# main2.net
KiCad netlist of a schematic drawn in EAGLE
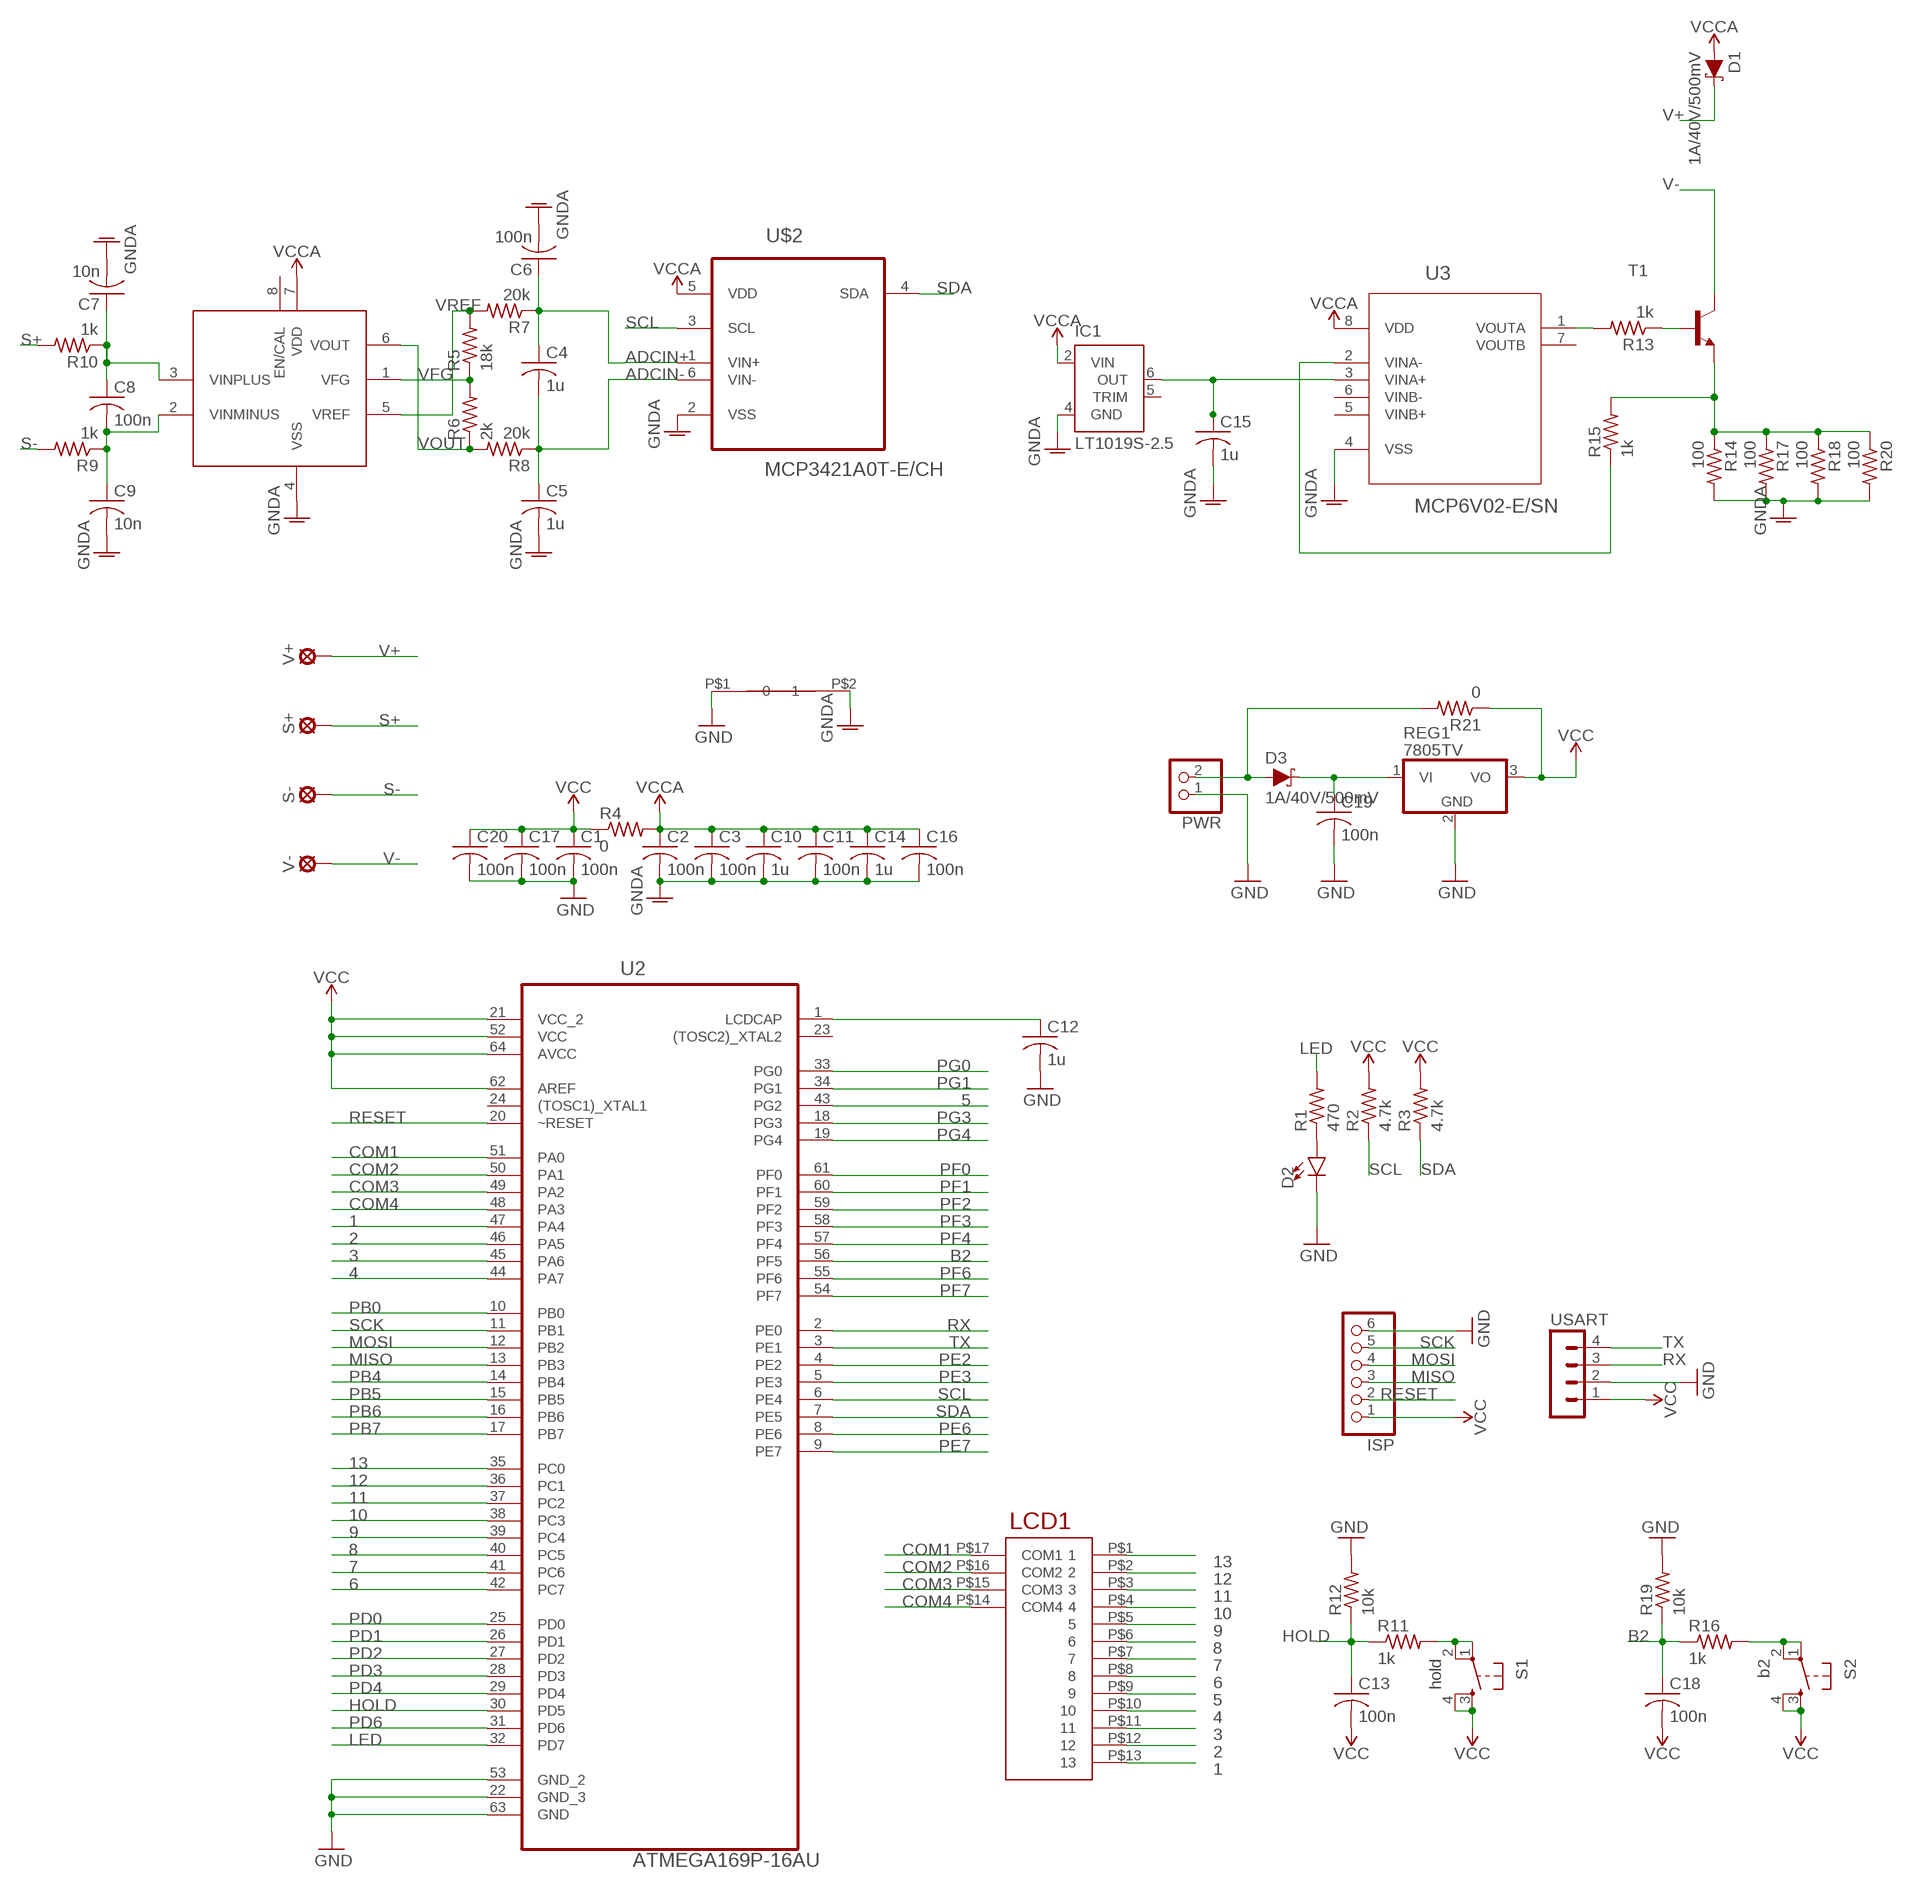
[diagram p0: schematic, sheet 1]

(export (version "E")
  (design (tool "Eeschema 10.0.6"))
  (components
    (comp (ref "C1")
      (value "100n")
      (footprint "eagle-import:C0603")
      (libsource (lib "eagle-import") (part "C-USC0603"))
    )
    (comp (ref "C2")
      (value "100n")
      (footprint "eagle-import:C0603")
      (libsource (lib "eagle-import") (part "C-USC0603"))
    )
    (comp (ref "C3")
      (value "100n")
      (footprint "eagle-import:C0603")
      (libsource (lib "eagle-import") (part "C-USC0603"))
    )
    (comp (ref "C4")
      (value "1u")
      (footprint "eagle-import:C0603")
      (libsource (lib "eagle-import") (part "C-USC0603"))
    )
    (comp (ref "C5")
      (value "1u")
      (footprint "eagle-import:C0603")
      (libsource (lib "eagle-import") (part "C-USC0603"))
    )
    (comp (ref "C6")
      (value "100n")
      (footprint "eagle-import:C0603")
      (libsource (lib "eagle-import") (part "C-USC0603"))
    )
    (comp (ref "C7")
      (value "10n")
      (footprint "eagle-import:C0603")
      (libsource (lib "eagle-import") (part "C-USC0603"))
    )
    (comp (ref "C8")
      (value "100n")
      (footprint "eagle-import:C0603")
      (libsource (lib "eagle-import") (part "C-USC0603"))
    )
    (comp (ref "C9")
      (value "10n")
      (footprint "eagle-import:C0603")
      (libsource (lib "eagle-import") (part "C-USC0603"))
    )
    (comp (ref "C10")
      (value "1u")
      (footprint "eagle-import:C0603")
      (libsource (lib "eagle-import") (part "C-USC0603"))
    )
    (comp (ref "C11")
      (value "100n")
      (footprint "eagle-import:C0603")
      (libsource (lib "eagle-import") (part "C-USC0603"))
    )
    (comp (ref "C12")
      (value "1u")
      (footprint "eagle-import:C0603")
      (libsource (lib "eagle-import") (part "C-USC0603"))
    )
    (comp (ref "C13")
      (value "100n")
      (footprint "eagle-import:C0603")
      (libsource (lib "eagle-import") (part "C-USC0603"))
    )
    (comp (ref "C14")
      (value "1u")
      (footprint "eagle-import:C0603")
      (libsource (lib "eagle-import") (part "C-USC0603"))
    )
    (comp (ref "C15")
      (value "1u")
      (footprint "eagle-import:C0603")
      (libsource (lib "eagle-import") (part "C-USC0603"))
    )
    (comp (ref "C16")
      (value "100n")
      (footprint "eagle-import:C0603")
      (libsource (lib "eagle-import") (part "C-USC0603"))
    )
    (comp (ref "C17")
      (value "100n")
      (footprint "eagle-import:C0603")
      (libsource (lib "eagle-import") (part "C-USC0603"))
    )
    (comp (ref "C18")
      (value "100n")
      (footprint "eagle-import:C0603")
      (libsource (lib "eagle-import") (part "C-USC0603"))
    )
    (comp (ref "C19")
      (value "100n")
      (footprint "eagle-import:C0603")
      (libsource (lib "eagle-import") (part "C-USC0603"))
    )
    (comp (ref "C20")
      (value "100n")
      (footprint "eagle-import:C0603")
      (libsource (lib "eagle-import") (part "C-USC0603"))
    )
    (comp (ref "D1")
      (value "1A/40V/500mV")
      (footprint "eagle-import:SMA-DIODE")
      (libsource (lib "eagle-import") (part "DIODE-SCHOTTKY-SS14"))
    )
    (comp (ref "D2")
      (value "LED5MM")
      (footprint "eagle-import:LED_5MM")
      (libsource (lib "eagle-import") (part "LED5MM"))
    )
    (comp (ref "D3")
      (value "1A/40V/500mV")
      (footprint "eagle-import:SMA-DIODE")
      (libsource (lib "eagle-import") (part "DIODE-SCHOTTKY-SS14"))
    )
    (comp (ref "IC1")
      (value "LT1019S-2.5")
      (footprint "eagle-import:SOIC8")
      (fields (field (name "MPN") "LT1019CS8-2.5#PBF"))
      (libsource (lib "eagle-import") (part "LT1019?S-2.5"))
    )
    (comp (ref "ISP")
      (value "PINHD-1X6")
      (footprint "eagle-import:1X06")
      (libsource (lib "eagle-import") (part "PINHD-1X6"))
    )
    (comp (ref "LCD1")
      (value "GDC0570_LCD")
      (footprint "eagle-import:GDC0570_LCD")
      (libsource (lib "eagle-import") (part "GDC0570_LCD"))
    )
    (comp (ref "PWR")
      (value "PINHD-1X2")
      (footprint "eagle-import:1X02")
      (libsource (lib "eagle-import") (part "PINHD-1X2"))
    )
    (comp (ref "R1")
      (value "470")
      (footprint "eagle-import:R0603")
      (libsource (lib "eagle-import") (part "R-US_R0603"))
    )
    (comp (ref "R2")
      (value "4.7k")
      (footprint "eagle-import:R0603")
      (libsource (lib "eagle-import") (part "R-US_R0603"))
    )
    (comp (ref "R3")
      (value "4.7k")
      (footprint "eagle-import:R0603")
      (libsource (lib "eagle-import") (part "R-US_R0603"))
    )
    (comp (ref "R4")
      (value "0")
      (footprint "eagle-import:0309_12")
      (libsource (lib "eagle-import") (part "R-US_0309/12"))
    )
    (comp (ref "R5")
      (value "18k")
      (footprint "eagle-import:R0603")
      (libsource (lib "eagle-import") (part "R-US_R0603"))
    )
    (comp (ref "R6")
      (value "2k")
      (footprint "eagle-import:R0603")
      (libsource (lib "eagle-import") (part "R-US_R0603"))
    )
    (comp (ref "R7")
      (value "20k")
      (footprint "eagle-import:R0603")
      (libsource (lib "eagle-import") (part "R-US_R0603"))
    )
    (comp (ref "R8")
      (value "20k")
      (footprint "eagle-import:R0603")
      (libsource (lib "eagle-import") (part "R-US_R0603"))
    )
    (comp (ref "R9")
      (value "1k")
      (footprint "eagle-import:R0603")
      (libsource (lib "eagle-import") (part "R-US_R0603"))
    )
    (comp (ref "R10")
      (value "1k")
      (footprint "eagle-import:R0603")
      (libsource (lib "eagle-import") (part "R-US_R0603"))
    )
    (comp (ref "R11")
      (value "1k")
      (footprint "eagle-import:R0603")
      (libsource (lib "eagle-import") (part "R-US_R0603"))
    )
    (comp (ref "R12")
      (value "10k")
      (footprint "eagle-import:R0603")
      (libsource (lib "eagle-import") (part "R-US_R0603"))
    )
    (comp (ref "R13")
      (value "1k")
      (footprint "eagle-import:R0603")
      (libsource (lib "eagle-import") (part "R-US_R0603"))
    )
    (comp (ref "R14")
      (value "100")
      (footprint "eagle-import:R0603")
      (libsource (lib "eagle-import") (part "R-US_R0603"))
    )
    (comp (ref "R15")
      (value "1k")
      (footprint "eagle-import:R0603")
      (libsource (lib "eagle-import") (part "R-US_R0603"))
    )
    (comp (ref "R16")
      (value "1k")
      (footprint "eagle-import:R0603")
      (libsource (lib "eagle-import") (part "R-US_R0603"))
    )
    (comp (ref "R17")
      (value "100")
      (footprint "eagle-import:R0603")
      (libsource (lib "eagle-import") (part "R-US_R0603"))
    )
    (comp (ref "R18")
      (value "100")
      (footprint "eagle-import:R0603")
      (libsource (lib "eagle-import") (part "R-US_R0603"))
    )
    (comp (ref "R19")
      (value "10k")
      (footprint "eagle-import:R0603")
      (libsource (lib "eagle-import") (part "R-US_R0603"))
    )
    (comp (ref "R20")
      (value "100")
      (footprint "eagle-import:R0603")
      (libsource (lib "eagle-import") (part "R-US_R0603"))
    )
    (comp (ref "R21")
      (value "0")
      (footprint "eagle-import:R0603")
      (libsource (lib "eagle-import") (part "R-US_R0603"))
    )
    (comp (ref "REG1")
      (value "7805TV")
      (footprint "eagle-import:TO220V")
      (libsource (lib "eagle-import") (part "78TV05"))
    )
    (comp (ref "S+")
      (value "MCS08")
      (footprint "eagle-import:MCS08")
      (libsource (lib "eagle-import") (part "MCS08"))
    )
    (comp (ref "S-")
      (value "MCS08")
      (footprint "eagle-import:MCS08")
      (libsource (lib "eagle-import") (part "MCS08"))
    )
    (comp (ref "S1")
      (value "hold")
      (footprint "eagle-import:TACTILE-PTH")
      (libsource (lib "eagle-import") (part "TAC_SWITCHPTH"))
    )
    (comp (ref "S2")
      (value "b2")
      (footprint "eagle-import:TACTILE-PTH")
      (libsource (lib "eagle-import") (part "TAC_SWITCHPTH"))
    )
    (comp (ref "T1")
      (value "MMBT3904LT1-NPN-SOT23-BEC")
      (footprint "eagle-import:SOT23-BEC")
      (libsource (lib "eagle-import") (part "-NPN-SOT23-BECMMBT3904LT1"))
    )
    (comp (ref "U$2")
      (value "MCP3421A0T-E/CH")
      (footprint "eagle-import:SOT95P270X145-6N")
      (libsource (lib "eagle-import") (part "MCP3421A0T-E/CH"))
    )
    (comp (ref "U$3")
      (value "MCP6N11")
      (footprint "eagle-import:SOIC8")
      (libsource (lib "eagle-import") (part "MCP6N11"))
    )
    (comp (ref "U$10")
      (value "SHORT32")
      (footprint "eagle-import:SHORT_32")
      (libsource (lib "eagle-import") (part "SHORT32"))
    )
    (comp (ref "U2")
      (value "ATMEGA169P-16AU")
      (footprint "eagle-import:QFP80P1600X1600X120-64N")
      (libsource (lib "eagle-import") (part "ATMEGA169P-16AU"))
    )
    (comp (ref "U3")
      (value "MCP6V02-E/SN")
      (footprint "eagle-import:SOIC127P600X175-8N")
      (libsource (lib "eagle-import") (part "MCP6V02-E/SN"))
    )
    (comp (ref "USART")
      (value "MA04-1")
      (footprint "eagle-import:MA04-1")
      (libsource (lib "eagle-import") (part "MA04-1"))
    )
    (comp (ref "V+")
      (value "MCS08")
      (footprint "eagle-import:MCS08")
      (libsource (lib "eagle-import") (part "MCS08"))
    )
    (comp (ref "V-")
      (value "MCS08")
      (footprint "eagle-import:MCS08")
      (libsource (lib "eagle-import") (part "MCS08"))
    )
  )
  (nets
    (net (code "1") (name "/1") (class "Default")
      (node (ref "LCD1") (pin "P$13") (pinfunction "13_P$13") (pintype "bidirectional"))
      (node (ref "U2") (pin "47") (pinfunction "PA4_47") (pintype "bidirectional"))
    )
    (net (code "2") (name "/2") (class "Default")
      (node (ref "LCD1") (pin "P$12") (pinfunction "12_P$12") (pintype "bidirectional"))
      (node (ref "U2") (pin "46") (pinfunction "PA5_46") (pintype "bidirectional"))
    )
    (net (code "3") (name "/3") (class "Default")
      (node (ref "LCD1") (pin "P$11") (pinfunction "11_P$11") (pintype "bidirectional"))
      (node (ref "U2") (pin "45") (pinfunction "PA6_45") (pintype "bidirectional"))
    )
    (net (code "4") (name "/4") (class "Default")
      (node (ref "LCD1") (pin "P$10") (pinfunction "10_P$10") (pintype "bidirectional"))
      (node (ref "U2") (pin "44") (pinfunction "PA7_44") (pintype "bidirectional"))
    )
    (net (code "5") (name "/5") (class "Default")
      (node (ref "LCD1") (pin "P$9") (pinfunction "9_P$9") (pintype "bidirectional"))
      (node (ref "U2") (pin "43") (pinfunction "PG2_43") (pintype "bidirectional"))
    )
    (net (code "6") (name "/6") (class "Default")
      (node (ref "LCD1") (pin "P$8") (pinfunction "8_P$8") (pintype "bidirectional"))
      (node (ref "U2") (pin "42") (pinfunction "PC7_42") (pintype "bidirectional"))
    )
    (net (code "7") (name "/7") (class "Default")
      (node (ref "LCD1") (pin "P$7") (pinfunction "7_P$7") (pintype "bidirectional"))
      (node (ref "U2") (pin "41") (pinfunction "PC6_41") (pintype "bidirectional"))
    )
    (net (code "8") (name "/8") (class "Default")
      (node (ref "LCD1") (pin "P$6") (pinfunction "6_P$6") (pintype "bidirectional"))
      (node (ref "U2") (pin "40") (pinfunction "PC5_40") (pintype "bidirectional"))
    )
    (net (code "9") (name "/9") (class "Default")
      (node (ref "LCD1") (pin "P$5") (pinfunction "5_P$5") (pintype "bidirectional"))
      (node (ref "U2") (pin "39") (pinfunction "PC4_39") (pintype "bidirectional"))
    )
    (net (code "10") (name "/10") (class "Default")
      (node (ref "LCD1") (pin "P$4") (pinfunction "4_P$4") (pintype "bidirectional"))
      (node (ref "U2") (pin "38") (pinfunction "PC3_38") (pintype "bidirectional"))
    )
    (net (code "11") (name "/11") (class "Default")
      (node (ref "LCD1") (pin "P$3") (pinfunction "3_P$3") (pintype "bidirectional"))
      (node (ref "U2") (pin "37") (pinfunction "PC2_37") (pintype "bidirectional"))
    )
    (net (code "12") (name "/12") (class "Default")
      (node (ref "LCD1") (pin "P$2") (pinfunction "2_P$2") (pintype "bidirectional"))
      (node (ref "U2") (pin "36") (pinfunction "PC1_36") (pintype "bidirectional"))
    )
    (net (code "13") (name "/13") (class "Default")
      (node (ref "LCD1") (pin "P$1") (pinfunction "1_P$1") (pintype "bidirectional"))
      (node (ref "U2") (pin "35") (pinfunction "PC0_35") (pintype "bidirectional"))
    )
    (net (code "14") (name "/ADCIN+") (class "Default")
      (node (ref "C4") (pin "1") (pinfunction "1_1") (pintype "passive"))
      (node (ref "C6") (pin "1") (pinfunction "1_1") (pintype "passive"))
      (node (ref "R7") (pin "1") (pinfunction "1_1") (pintype "passive"))
      (node (ref "U$2") (pin "1") (pinfunction "VIN+_1") (pintype "input"))
    )
    (net (code "15") (name "/ADCIN-") (class "Default")
      (node (ref "C4") (pin "2") (pinfunction "2_2") (pintype "passive"))
      (node (ref "C5") (pin "1") (pinfunction "1_1") (pintype "passive"))
      (node (ref "R8") (pin "1") (pinfunction "1_1") (pintype "passive"))
      (node (ref "U$2") (pin "6") (pinfunction "VIN-_6") (pintype "input"))
    )
    (net (code "16") (name "/B2") (class "Default")
      (node (ref "C18") (pin "1") (pinfunction "1_1") (pintype "passive"))
      (node (ref "R16") (pin "1") (pinfunction "1_1") (pintype "passive"))
      (node (ref "R19") (pin "1") (pinfunction "1_1") (pintype "passive"))
      (node (ref "U2") (pin "56") (pinfunction "PF5_56") (pintype "bidirectional"))
    )
    (net (code "17") (name "/COM1") (class "Default")
      (node (ref "LCD1") (pin "P$17") (pinfunction "COM1_P$17") (pintype "bidirectional"))
      (node (ref "U2") (pin "51") (pinfunction "PA0_51") (pintype "bidirectional"))
    )
    (net (code "18") (name "/COM2") (class "Default")
      (node (ref "LCD1") (pin "P$16") (pinfunction "COM2_P$16") (pintype "bidirectional"))
      (node (ref "U2") (pin "50") (pinfunction "PA1_50") (pintype "bidirectional"))
    )
    (net (code "19") (name "/COM3") (class "Default")
      (node (ref "LCD1") (pin "P$15") (pinfunction "COM3_P$15") (pintype "bidirectional"))
      (node (ref "U2") (pin "49") (pinfunction "PA2_49") (pintype "bidirectional"))
    )
    (net (code "20") (name "/COM4") (class "Default")
      (node (ref "LCD1") (pin "P$14") (pinfunction "COM4_P$14") (pintype "bidirectional"))
      (node (ref "U2") (pin "48") (pinfunction "PA3_48") (pintype "bidirectional"))
    )
    (net (code "21") (name "/HOLD") (class "Default")
      (node (ref "C13") (pin "1") (pinfunction "1_1") (pintype "passive"))
      (node (ref "R11") (pin "1") (pinfunction "1_1") (pintype "passive"))
      (node (ref "R12") (pin "1") (pinfunction "1_1") (pintype "passive"))
      (node (ref "U2") (pin "30") (pinfunction "PD5_30") (pintype "bidirectional"))
    )
    (net (code "22") (name "/LED") (class "Default")
      (node (ref "R1") (pin "2") (pinfunction "2_2") (pintype "passive"))
      (node (ref "U2") (pin "32") (pinfunction "PD7_32") (pintype "bidirectional"))
    )
    (net (code "23") (name "/MISO") (class "Default")
      (node (ref "ISP") (pin "3") (pinfunction "3_3") (pintype "passive"))
      (node (ref "U2") (pin "13") (pinfunction "PB3_13") (pintype "bidirectional"))
    )
    (net (code "24") (name "/MOSI") (class "Default")
      (node (ref "ISP") (pin "4") (pinfunction "4_4") (pintype "passive"))
      (node (ref "U2") (pin "12") (pinfunction "PB2_12") (pintype "bidirectional"))
    )
    (net (code "25") (name "/PB0") (class "Default")
      (node (ref "U2") (pin "10") (pinfunction "PB0_10") (pintype "bidirectional"))
    )
    (net (code "26") (name "/PB4") (class "Default")
      (node (ref "U2") (pin "14") (pinfunction "PB4_14") (pintype "bidirectional"))
    )
    (net (code "27") (name "/PB5") (class "Default")
      (node (ref "U2") (pin "15") (pinfunction "PB5_15") (pintype "bidirectional"))
    )
    (net (code "28") (name "/PB6") (class "Default")
      (node (ref "U2") (pin "16") (pinfunction "PB6_16") (pintype "bidirectional"))
    )
    (net (code "29") (name "/PB7") (class "Default")
      (node (ref "U2") (pin "17") (pinfunction "PB7_17") (pintype "bidirectional"))
    )
    (net (code "30") (name "/PD0") (class "Default")
      (node (ref "U2") (pin "25") (pinfunction "PD0_25") (pintype "bidirectional"))
    )
    (net (code "31") (name "/PD1") (class "Default")
      (node (ref "U2") (pin "26") (pinfunction "PD1_26") (pintype "bidirectional"))
    )
    (net (code "32") (name "/PD2") (class "Default")
      (node (ref "U2") (pin "27") (pinfunction "PD2_27") (pintype "bidirectional"))
    )
    (net (code "33") (name "/PD3") (class "Default")
      (node (ref "U2") (pin "28") (pinfunction "PD3_28") (pintype "bidirectional"))
    )
    (net (code "34") (name "/PD4") (class "Default")
      (node (ref "U2") (pin "29") (pinfunction "PD4_29") (pintype "bidirectional"))
    )
    (net (code "35") (name "/PD6") (class "Default")
      (node (ref "U2") (pin "31") (pinfunction "PD6_31") (pintype "bidirectional"))
    )
    (net (code "36") (name "/PE2") (class "Default")
      (node (ref "U2") (pin "4") (pinfunction "PE2_4") (pintype "bidirectional"))
    )
    (net (code "37") (name "/PE3") (class "Default")
      (node (ref "U2") (pin "5") (pinfunction "PE3_5") (pintype "bidirectional"))
    )
    (net (code "38") (name "/PE6") (class "Default")
      (node (ref "U2") (pin "8") (pinfunction "PE6_8") (pintype "bidirectional"))
    )
    (net (code "39") (name "/PE7") (class "Default")
      (node (ref "U2") (pin "9") (pinfunction "PE7_9") (pintype "bidirectional"))
    )
    (net (code "40") (name "/PF0") (class "Default")
      (node (ref "U2") (pin "61") (pinfunction "PF0_61") (pintype "bidirectional"))
    )
    (net (code "41") (name "/PF1") (class "Default")
      (node (ref "U2") (pin "60") (pinfunction "PF1_60") (pintype "bidirectional"))
    )
    (net (code "42") (name "/PF2") (class "Default")
      (node (ref "U2") (pin "59") (pinfunction "PF2_59") (pintype "bidirectional"))
    )
    (net (code "43") (name "/PF3") (class "Default")
      (node (ref "U2") (pin "58") (pinfunction "PF3_58") (pintype "bidirectional"))
    )
    (net (code "44") (name "/PF4") (class "Default")
      (node (ref "U2") (pin "57") (pinfunction "PF4_57") (pintype "bidirectional"))
    )
    (net (code "45") (name "/PF6") (class "Default")
      (node (ref "U2") (pin "55") (pinfunction "PF6_55") (pintype "bidirectional"))
    )
    (net (code "46") (name "/PF7") (class "Default")
      (node (ref "U2") (pin "54") (pinfunction "PF7_54") (pintype "bidirectional"))
    )
    (net (code "47") (name "/PG0") (class "Default")
      (node (ref "U2") (pin "33") (pinfunction "PG0_33") (pintype "bidirectional"))
    )
    (net (code "48") (name "/PG1") (class "Default")
      (node (ref "U2") (pin "34") (pinfunction "PG1_34") (pintype "bidirectional"))
    )
    (net (code "49") (name "/PG3") (class "Default")
      (node (ref "U2") (pin "18") (pinfunction "PG3_18") (pintype "bidirectional"))
    )
    (net (code "50") (name "/PG4") (class "Default")
      (node (ref "U2") (pin "19") (pinfunction "PG4_19") (pintype "bidirectional"))
    )
    (net (code "51") (name "/RESET") (class "Default")
      (node (ref "ISP") (pin "2") (pinfunction "2_2") (pintype "passive"))
      (node (ref "U2") (pin "20") (pinfunction "~{RESET}_20") (pintype "input"))
    )
    (net (code "52") (name "/RX") (class "Default")
      (node (ref "U2") (pin "2") (pinfunction "PE0_2") (pintype "bidirectional"))
      (node (ref "USART") (pin "3") (pinfunction "3_3") (pintype "passive"))
    )
    (net (code "53") (name "/S+") (class "Default")
      (node (ref "R10") (pin "2") (pinfunction "2_2") (pintype "passive"))
      (node (ref "S+") (pin "MP") (pinfunction "MP_MP") (pintype "passive"))
    )
    (net (code "54") (name "/S-") (class "Default")
      (node (ref "R9") (pin "2") (pinfunction "2_2") (pintype "passive"))
      (node (ref "S-") (pin "MP") (pinfunction "MP_MP") (pintype "passive"))
    )
    (net (code "55") (name "/SCK") (class "Default")
      (node (ref "ISP") (pin "5") (pinfunction "5_5") (pintype "passive"))
      (node (ref "U2") (pin "11") (pinfunction "PB1_11") (pintype "bidirectional"))
    )
    (net (code "56") (name "/SCL") (class "Default")
      (node (ref "R2") (pin "1") (pinfunction "1_1") (pintype "passive"))
      (node (ref "U$2") (pin "3") (pinfunction "SCL_3") (pintype "input"))
      (node (ref "U2") (pin "6") (pinfunction "PE4_6") (pintype "bidirectional"))
    )
    (net (code "57") (name "/SDA") (class "Default")
      (node (ref "R3") (pin "1") (pinfunction "1_1") (pintype "passive"))
      (node (ref "U$2") (pin "4") (pinfunction "SDA_4") (pintype "bidirectional"))
      (node (ref "U2") (pin "7") (pinfunction "PE5_7") (pintype "bidirectional"))
    )
    (net (code "58") (name "/TX") (class "Default")
      (node (ref "U2") (pin "3") (pinfunction "PE1_3") (pintype "bidirectional"))
      (node (ref "USART") (pin "4") (pinfunction "4_4") (pintype "passive"))
    )
    (net (code "59") (name "/V+") (class "Default")
      (node (ref "D1") (pin "C") (pinfunction "C_C") (pintype "passive"))
      (node (ref "V+") (pin "MP") (pinfunction "MP_MP") (pintype "passive"))
    )
    (net (code "60") (name "/V-") (class "Default")
      (node (ref "T1") (pin "C") (pinfunction "C_C") (pintype "passive"))
      (node (ref "V-") (pin "MP") (pinfunction "MP_MP") (pintype "passive"))
    )
    (net (code "61") (name "/VFG") (class "Default")
      (node (ref "R5") (pin "1") (pinfunction "1_1") (pintype "passive"))
      (node (ref "R6") (pin "2") (pinfunction "2_2") (pintype "passive"))
      (node (ref "U$3") (pin "1") (pinfunction "VFG_1") (pintype "bidirectional"))
    )
    (net (code "62") (name "/VOUT") (class "Default")
      (node (ref "R6") (pin "1") (pinfunction "1_1") (pintype "passive"))
      (node (ref "R8") (pin "2") (pinfunction "2_2") (pintype "passive"))
      (node (ref "U$3") (pin "6") (pinfunction "VOUT_6") (pintype "bidirectional"))
    )
    (net (code "63") (name "/VREF") (class "Default")
      (node (ref "R5") (pin "2") (pinfunction "2_2") (pintype "passive"))
      (node (ref "R7") (pin "2") (pinfunction "2_2") (pintype "passive"))
      (node (ref "U$3") (pin "5") (pinfunction "VREF_5") (pintype "bidirectional"))
    )
    (net (code "64") (name "GND") (class "Default")
      (node (ref "C1") (pin "2") (pinfunction "2_2") (pintype "passive"))
      (node (ref "C12") (pin "2") (pinfunction "2_2") (pintype "passive"))
      (node (ref "C17") (pin "2") (pinfunction "2_2") (pintype "passive"))
      (node (ref "C19") (pin "2") (pinfunction "2_2") (pintype "passive"))
      (node (ref "C20") (pin "2") (pinfunction "2_2") (pintype "passive"))
      (node (ref "D2") (pin "K") (pinfunction "C_K") (pintype "passive"))
      (node (ref "ISP") (pin "6") (pinfunction "6_6") (pintype "passive"))
      (node (ref "PWR") (pin "1") (pinfunction "1_1") (pintype "passive"))
      (node (ref "R12") (pin "2") (pinfunction "2_2") (pintype "passive"))
      (node (ref "R19") (pin "2") (pinfunction "2_2") (pintype "passive"))
      (node (ref "REG1") (pin "2") (pinfunction "GND_2") (pintype "passive"))
      (node (ref "U$10") (pin "P$1") (pinfunction "0_P$1") (pintype "bidirectional"))
      (node (ref "U2") (pin "22") (pinfunction "GND_3_22") (pintype "passive"))
      (node (ref "U2") (pin "53") (pinfunction "GND_2_53") (pintype "passive"))
      (node (ref "U2") (pin "63") (pinfunction "GND_63") (pintype "passive"))
      (node (ref "USART") (pin "2") (pinfunction "2_2") (pintype "passive"))
    )
    (net (code "65") (name "GNDA") (class "Default")
      (node (ref "C10") (pin "2") (pinfunction "2_2") (pintype "passive"))
      (node (ref "C11") (pin "2") (pinfunction "2_2") (pintype "passive"))
      (node (ref "C14") (pin "2") (pinfunction "2_2") (pintype "passive"))
      (node (ref "C15") (pin "2") (pinfunction "2_2") (pintype "passive"))
      (node (ref "C16") (pin "2") (pinfunction "2_2") (pintype "passive"))
      (node (ref "C2") (pin "2") (pinfunction "2_2") (pintype "passive"))
      (node (ref "C3") (pin "2") (pinfunction "2_2") (pintype "passive"))
      (node (ref "C5") (pin "2") (pinfunction "2_2") (pintype "passive"))
      (node (ref "C6") (pin "2") (pinfunction "2_2") (pintype "passive"))
      (node (ref "C7") (pin "2") (pinfunction "2_2") (pintype "passive"))
      (node (ref "C9") (pin "2") (pinfunction "2_2") (pintype "passive"))
      (node (ref "IC1") (pin "4") (pinfunction "GND_4") (pintype "power_in"))
      (node (ref "R14") (pin "2") (pinfunction "2_2") (pintype "passive"))
      (node (ref "R17") (pin "2") (pinfunction "2_2") (pintype "passive"))
      (node (ref "R18") (pin "2") (pinfunction "2_2") (pintype "passive"))
      (node (ref "R20") (pin "2") (pinfunction "2_2") (pintype "passive"))
      (node (ref "U$10") (pin "P$2") (pinfunction "1_P$2") (pintype "bidirectional"))
      (node (ref "U$2") (pin "2") (pinfunction "VSS_2") (pintype "passive"))
      (node (ref "U$3") (pin "4") (pinfunction "VSS_4") (pintype "bidirectional"))
      (node (ref "U3") (pin "4") (pinfunction "VSS_4") (pintype "power_in"))
    )
    (net (code "66") (name "Net-(D2-PadA)") (class "Default")
      (node (ref "D2") (pin "A") (pinfunction "A_A") (pintype "passive"))
      (node (ref "R1") (pin "1") (pinfunction "1_1") (pintype "passive"))
    )
    (net (code "67") (name "Net-(D3-PadA)") (class "Default")
      (node (ref "D3") (pin "A") (pinfunction "A_A") (pintype "passive"))
      (node (ref "PWR") (pin "2") (pinfunction "2_2") (pintype "passive"))
      (node (ref "R21") (pin "2") (pinfunction "2_2") (pintype "passive"))
    )
    (net (code "68") (name "Net-(IC1-OUT)") (class "Default")
      (node (ref "C15") (pin "1") (pinfunction "1_1") (pintype "passive"))
      (node (ref "IC1") (pin "6") (pinfunction "OUT_6") (pintype "input"))
      (node (ref "U3") (pin "3") (pinfunction "VINA+_3") (pintype "input"))
    )
    (net (code "69") (name "Net-(R11-Pad2)") (class "Default")
      (node (ref "R11") (pin "2") (pinfunction "2_2") (pintype "passive"))
      (node (ref "S1") (pin "1") (pinfunction "1_1") (pintype "passive"))
      (node (ref "S1") (pin "2") (pinfunction "2_2") (pintype "passive"))
    )
    (net (code "70") (name "Net-(R13-Pad1)") (class "Default")
      (node (ref "R13") (pin "1") (pinfunction "1_1") (pintype "passive"))
      (node (ref "T1") (pin "B") (pinfunction "B_B") (pintype "passive"))
    )
    (net (code "71") (name "Net-(R14-Pad1)") (class "Default")
      (node (ref "R14") (pin "1") (pinfunction "1_1") (pintype "passive"))
      (node (ref "R15") (pin "2") (pinfunction "2_2") (pintype "passive"))
      (node (ref "R17") (pin "1") (pinfunction "1_1") (pintype "passive"))
      (node (ref "R18") (pin "1") (pinfunction "1_1") (pintype "passive"))
      (node (ref "R20") (pin "1") (pinfunction "1_1") (pintype "passive"))
      (node (ref "T1") (pin "E") (pinfunction "E_E") (pintype "passive"))
    )
    (net (code "72") (name "Net-(R16-Pad2)") (class "Default")
      (node (ref "R16") (pin "2") (pinfunction "2_2") (pintype "passive"))
      (node (ref "S2") (pin "1") (pinfunction "1_1") (pintype "passive"))
      (node (ref "S2") (pin "2") (pinfunction "2_2") (pintype "passive"))
    )
    (net (code "73") (name "Net-(REG1-VI)") (class "Default")
      (node (ref "C19") (pin "1") (pinfunction "1_1") (pintype "passive"))
      (node (ref "D3") (pin "C") (pinfunction "C_C") (pintype "passive"))
      (node (ref "REG1") (pin "1") (pinfunction "VI_1") (pintype "input"))
    )
    (net (code "74") (name "Net-(U$3-VINMINUS)") (class "Default")
      (node (ref "C8") (pin "2") (pinfunction "2_2") (pintype "passive"))
      (node (ref "C9") (pin "1") (pinfunction "1_1") (pintype "passive"))
      (node (ref "R9") (pin "1") (pinfunction "1_1") (pintype "passive"))
      (node (ref "U$3") (pin "2") (pinfunction "VINMINUS_2") (pintype "bidirectional"))
    )
    (net (code "75") (name "Net-(U$3-VINPLUS)") (class "Default")
      (node (ref "C7") (pin "1") (pinfunction "1_1") (pintype "passive"))
      (node (ref "C8") (pin "1") (pinfunction "1_1") (pintype "passive"))
      (node (ref "R10") (pin "1") (pinfunction "1_1") (pintype "passive"))
      (node (ref "U$3") (pin "3") (pinfunction "VINPLUS_3") (pintype "bidirectional"))
    )
    (net (code "76") (name "Net-(U2-LCDCAP)") (class "Default")
      (node (ref "C12") (pin "1") (pinfunction "1_1") (pintype "passive"))
      (node (ref "U2") (pin "1") (pinfunction "LCDCAP_1") (pintype "passive"))
    )
    (net (code "77") (name "Net-(U3-VINA-)") (class "Default")
      (node (ref "R15") (pin "1") (pinfunction "1_1") (pintype "passive"))
      (node (ref "U3") (pin "2") (pinfunction "VINA-_2") (pintype "input"))
    )
    (net (code "78") (name "Net-(U3-VOUTA)") (class "Default")
      (node (ref "R13") (pin "2") (pinfunction "2_2") (pintype "passive"))
      (node (ref "U3") (pin "1") (pinfunction "VOUTA_1") (pintype "output"))
    )
    (net (code "79") (name "VCC") (class "Default")
      (node (ref "C1") (pin "1") (pinfunction "1_1") (pintype "passive"))
      (node (ref "C13") (pin "2") (pinfunction "2_2") (pintype "passive"))
      (node (ref "C17") (pin "1") (pinfunction "1_1") (pintype "passive"))
      (node (ref "C18") (pin "2") (pinfunction "2_2") (pintype "passive"))
      (node (ref "C20") (pin "1") (pinfunction "1_1") (pintype "passive"))
      (node (ref "ISP") (pin "1") (pinfunction "1_1") (pintype "passive"))
      (node (ref "R2") (pin "2") (pinfunction "2_2") (pintype "passive"))
      (node (ref "R21") (pin "1") (pinfunction "1_1") (pintype "passive"))
      (node (ref "R3") (pin "2") (pinfunction "2_2") (pintype "passive"))
      (node (ref "R4") (pin "1") (pinfunction "1_1") (pintype "passive"))
      (node (ref "REG1") (pin "3") (pinfunction "VO_3") (pintype "passive"))
      (node (ref "S1") (pin "3") (pinfunction "3_3") (pintype "passive"))
      (node (ref "S1") (pin "4") (pinfunction "4_4") (pintype "passive"))
      (node (ref "S2") (pin "3") (pinfunction "3_3") (pintype "passive"))
      (node (ref "S2") (pin "4") (pinfunction "4_4") (pintype "passive"))
      (node (ref "U2") (pin "21") (pinfunction "VCC_2_21") (pintype "power_in"))
      (node (ref "U2") (pin "52") (pinfunction "VCC_52") (pintype "power_in"))
      (node (ref "U2") (pin "62") (pinfunction "AREF_62") (pintype "input"))
      (node (ref "U2") (pin "64") (pinfunction "AVCC_64") (pintype "power_in"))
      (node (ref "USART") (pin "1") (pinfunction "1_1") (pintype "passive"))
    )
    (net (code "80") (name "VCCA") (class "Default")
      (node (ref "C10") (pin "1") (pinfunction "1_1") (pintype "passive"))
      (node (ref "C11") (pin "1") (pinfunction "1_1") (pintype "passive"))
      (node (ref "C14") (pin "1") (pinfunction "1_1") (pintype "passive"))
      (node (ref "C16") (pin "1") (pinfunction "1_1") (pintype "passive"))
      (node (ref "C2") (pin "1") (pinfunction "1_1") (pintype "passive"))
      (node (ref "C3") (pin "1") (pinfunction "1_1") (pintype "passive"))
      (node (ref "D1") (pin "A") (pinfunction "A_A") (pintype "passive"))
      (node (ref "IC1") (pin "2") (pinfunction "VIN_2") (pintype "input"))
      (node (ref "R4") (pin "2") (pinfunction "2_2") (pintype "passive"))
      (node (ref "U$2") (pin "5") (pinfunction "VDD_5") (pintype "power_in"))
      (node (ref "U$3") (pin "7") (pinfunction "VDD_7") (pintype "bidirectional"))
      (node (ref "U3") (pin "8") (pinfunction "VDD_8") (pintype "power_in"))
    )
    (net (code "81") (name "unconnected-(IC1-TRIM-Pad5)") (class "Default")
      (node (ref "IC1") (pin "5") (pinfunction "TRIM_5") (pintype "passive"))
    )
    (net (code "82") (name "unconnected-(U$3-EN{slash}CAL-Pad8)") (class "Default")
      (node (ref "U$3") (pin "8") (pinfunction "EN/CAL_8") (pintype "bidirectional"))
    )
    (net (code "83") (name "unconnected-(U2-(TOSC1)_XTAL1-Pad24)") (class "Default")
      (node (ref "U2") (pin "24") (pinfunction "(TOSC1)_XTAL1_24") (pintype "input"))
    )
    (net (code "84") (name "unconnected-(U2-(TOSC2)_XTAL2-Pad23)") (class "Default")
      (node (ref "U2") (pin "23") (pinfunction "(TOSC2)_XTAL2_23") (pintype "output"))
    )
    (net (code "85") (name "unconnected-(U3-VINB+-Pad5)") (class "Default")
      (node (ref "U3") (pin "5") (pinfunction "VINB+_5") (pintype "input"))
    )
    (net (code "86") (name "unconnected-(U3-VINB--Pad6)") (class "Default")
      (node (ref "U3") (pin "6") (pinfunction "VINB-_6") (pintype "input"))
    )
    (net (code "87") (name "unconnected-(U3-VOUTB-Pad7)") (class "Default")
      (node (ref "U3") (pin "7") (pinfunction "VOUTB_7") (pintype "output"))
    )
  )
)
